# AD4111_2.net
KiCad netlist of a schematic drawn in Altium Designer
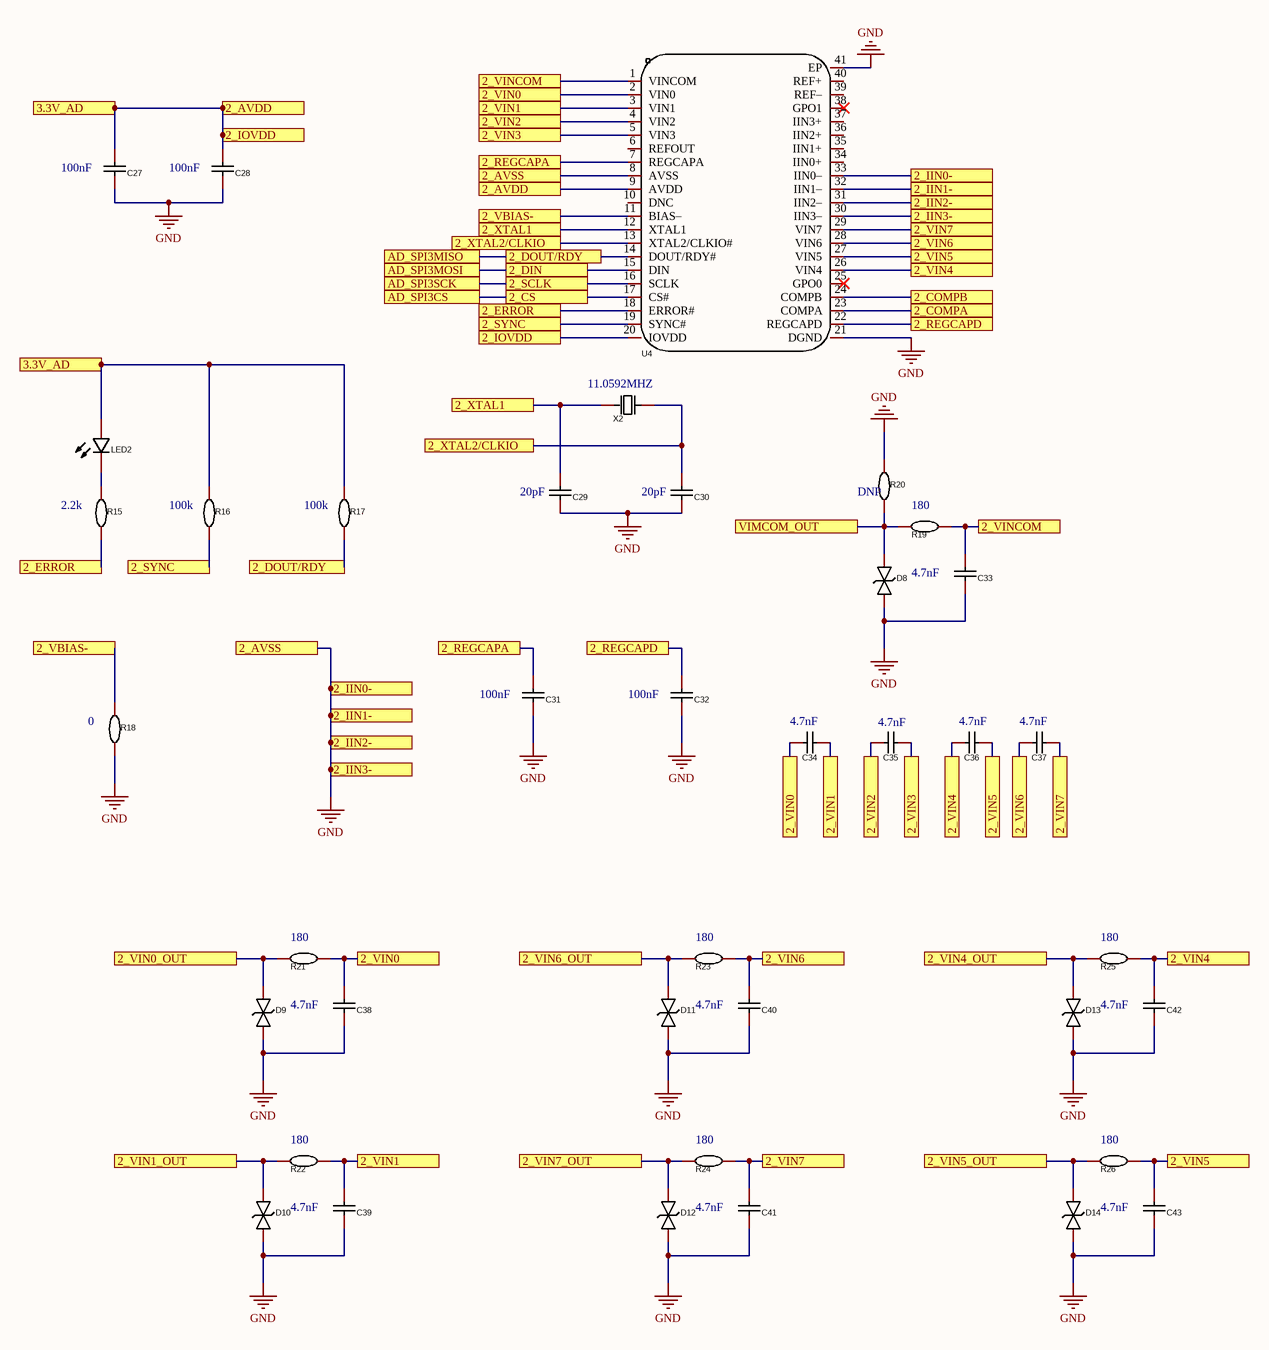
[diagram p0: AD4111_2.SchDoc]

(export (version "E")
  (design (tool "Eeschema 10.0.6"))
  (components
    (comp (ref "C27")
      (value "100nF")
      (footprint "C0603")
      (description "0603电容")
      (fields (field (name "MANUFACTURER") "FH(风华)") (field (name "MANUFACTURER PART") "0603B104K500NT"))
      (libsource (lib "LC_Components") (part "0603B104K500NT"))
    )
    (comp (ref "C28")
      (value "100nF")
      (footprint "C0603")
      (description "0603电容")
      (fields (field (name "MANUFACTURER") "FH(风华)") (field (name "MANUFACTURER PART") "0603B104K500NT"))
      (libsource (lib "LC_Components") (part "0603B104K500NT"))
    )
    (comp (ref "C29")
      (value "20pF")
      (footprint "C0603")
      (description "0603电容")
      (fields (field (name "MANUFACTURER") "FH(风华)") (field (name "MANUFACTURER PART") "0603B104K500NT"))
      (libsource (lib "LC_Components") (part "0603B104K500NT"))
    )
    (comp (ref "C30")
      (value "20pF")
      (footprint "C0603")
      (description "0603电容")
      (fields (field (name "MANUFACTURER") "FH(风华)") (field (name "MANUFACTURER PART") "0603B104K500NT"))
      (libsource (lib "LC_Components") (part "0603B104K500NT"))
    )
    (comp (ref "C31")
      (value "100nF")
      (footprint "C0603")
      (description "0603电容")
      (fields (field (name "MANUFACTURER") "FH(风华)") (field (name "MANUFACTURER PART") "0603B104K500NT"))
      (libsource (lib "LC_Components") (part "0603B104K500NT"))
    )
    (comp (ref "C32")
      (value "100nF")
      (footprint "C0603")
      (description "0603电容")
      (fields (field (name "MANUFACTURER") "FH(风华)") (field (name "MANUFACTURER PART") "0603B104K500NT"))
      (libsource (lib "LC_Components") (part "0603B104K500NT"))
    )
    (comp (ref "C33")
      (value "4.7nF")
      (footprint "C0603")
      (description "0603电容")
      (fields (field (name "MANUFACTURER") "FH(风华)") (field (name "MANUFACTURER PART") "0603B104K500NT"))
      (libsource (lib "LC_Components") (part "0603B104K500NT"))
    )
    (comp (ref "C34")
      (value "4.7nF")
      (footprint "C0603")
      (description "0603电容")
      (fields (field (name "MANUFACTURER") "FH(风华)") (field (name "MANUFACTURER PART") "0603B104K500NT"))
      (libsource (lib "LC_Components") (part "0603B104K500NT"))
    )
    (comp (ref "C35")
      (value "4.7nF")
      (footprint "C0603")
      (description "0603电容")
      (fields (field (name "MANUFACTURER") "FH(风华)") (field (name "MANUFACTURER PART") "0603B104K500NT"))
      (libsource (lib "LC_Components") (part "0603B104K500NT"))
    )
    (comp (ref "C36")
      (value "4.7nF")
      (footprint "C0603")
      (description "0603电容")
      (fields (field (name "MANUFACTURER") "FH(风华)") (field (name "MANUFACTURER PART") "0603B104K500NT"))
      (libsource (lib "LC_Components") (part "0603B104K500NT"))
    )
    (comp (ref "C37")
      (value "4.7nF")
      (footprint "C0603")
      (description "0603电容")
      (fields (field (name "MANUFACTURER") "FH(风华)") (field (name "MANUFACTURER PART") "0603B104K500NT"))
      (libsource (lib "LC_Components") (part "0603B104K500NT"))
    )
    (comp (ref "C38")
      (value "4.7nF")
      (footprint "C0603")
      (description "0603电容")
      (fields (field (name "MANUFACTURER") "FH(风华)") (field (name "MANUFACTURER PART") "0603B104K500NT"))
      (libsource (lib "LC_Components") (part "0603B104K500NT"))
    )
    (comp (ref "C39")
      (value "4.7nF")
      (footprint "C0603")
      (description "0603电容")
      (fields (field (name "MANUFACTURER") "FH(风华)") (field (name "MANUFACTURER PART") "0603B104K500NT"))
      (libsource (lib "LC_Components") (part "0603B104K500NT"))
    )
    (comp (ref "C40")
      (value "4.7nF")
      (footprint "C0603")
      (description "0603电容")
      (fields (field (name "MANUFACTURER") "FH(风华)") (field (name "MANUFACTURER PART") "0603B104K500NT"))
      (libsource (lib "LC_Components") (part "0603B104K500NT"))
    )
    (comp (ref "C41")
      (value "4.7nF")
      (footprint "C0603")
      (description "0603电容")
      (fields (field (name "MANUFACTURER") "FH(风华)") (field (name "MANUFACTURER PART") "0603B104K500NT"))
      (libsource (lib "LC_Components") (part "0603B104K500NT"))
    )
    (comp (ref "C42")
      (value "4.7nF")
      (footprint "C0603")
      (description "0603电容")
      (fields (field (name "MANUFACTURER") "FH(风华)") (field (name "MANUFACTURER PART") "0603B104K500NT"))
      (libsource (lib "LC_Components") (part "0603B104K500NT"))
    )
    (comp (ref "C43")
      (value "4.7nF")
      (footprint "C0603")
      (description "0603电容")
      (fields (field (name "MANUFACTURER") "FH(风华)") (field (name "MANUFACTURER PART") "0603B104K500NT"))
      (libsource (lib "LC_Components") (part "0603B104K500NT"))
    )
    (comp (ref "D8")
      (value "SMAJ33CA_C908829")
      (footprint "SMA_L4.4-W2.8-LS5.1-BI")
      (description "SMAJ33CA")
      (fields (field (name "MANUFACTURER") "GOODWORK(固得沃克)"))
      (libsource (lib "LC_Components") (part "SMAJ33CA_C908829"))
    )
    (comp (ref "D9")
      (value "SMAJ33CA_C908829")
      (footprint "SMA_L4.4-W2.8-LS5.1-BI")
      (description "SMAJ33CA")
      (fields (field (name "MANUFACTURER") "GOODWORK(固得沃克)"))
      (libsource (lib "LC_Components") (part "SMAJ33CA_C908829"))
    )
    (comp (ref "D10")
      (value "SMAJ33CA_C908829")
      (footprint "SMA_L4.4-W2.8-LS5.1-BI")
      (description "SMAJ33CA")
      (fields (field (name "MANUFACTURER") "GOODWORK(固得沃克)"))
      (libsource (lib "LC_Components") (part "SMAJ33CA_C908829"))
    )
    (comp (ref "D11")
      (value "SMAJ33CA_C908829")
      (footprint "SMA_L4.4-W2.8-LS5.1-BI")
      (description "SMAJ33CA")
      (fields (field (name "MANUFACTURER") "GOODWORK(固得沃克)"))
      (libsource (lib "LC_Components") (part "SMAJ33CA_C908829"))
    )
    (comp (ref "D12")
      (value "SMAJ33CA_C908829")
      (footprint "SMA_L4.4-W2.8-LS5.1-BI")
      (description "SMAJ33CA")
      (fields (field (name "MANUFACTURER") "GOODWORK(固得沃克)"))
      (libsource (lib "LC_Components") (part "SMAJ33CA_C908829"))
    )
    (comp (ref "D13")
      (value "SMAJ33CA_C908829")
      (footprint "SMA_L4.4-W2.8-LS5.1-BI")
      (description "SMAJ33CA")
      (fields (field (name "MANUFACTURER") "GOODWORK(固得沃克)"))
      (libsource (lib "LC_Components") (part "SMAJ33CA_C908829"))
    )
    (comp (ref "D14")
      (value "SMAJ33CA_C908829")
      (footprint "SMA_L4.4-W2.8-LS5.1-BI")
      (description "SMAJ33CA")
      (fields (field (name "MANUFACTURER") "GOODWORK(固得沃克)"))
      (libsource (lib "LC_Components") (part "SMAJ33CA_C908829"))
    )
    (comp (ref "LED2")
      (value "NCD0603R1_C84263")
      (footprint "LED0603-RD_RED")
      (description "LED")
      (fields (field (name "MANUFACTURER") "国星光电") (field (name "MANUFACTURER PART") "NCD0603R1"))
      (libsource (lib "LC_Components") (part "NCD0603R1_C84263"))
    )
    (comp (ref "R15")
      (value "2.2k")
      (footprint "R0603")
      (description "0603电阻")
      (fields
        (field (name "MANUFACTURER") "UNI-ROYAL(厚声)")
        (field (name "MANUFACTURER PART") "0603WAF1002T5E")
      )
      (libsource (lib "LC_Components") (part "0603WAF1002T5E"))
    )
    (comp (ref "R16")
      (value "100k")
      (footprint "R0603")
      (description "0603电阻")
      (fields
        (field (name "MANUFACTURER") "UNI-ROYAL(厚声)")
        (field (name "MANUFACTURER PART") "0603WAF1002T5E")
      )
      (libsource (lib "LC_Components") (part "0603WAF1002T5E"))
    )
    (comp (ref "R17")
      (value "100k")
      (footprint "R0603")
      (description "0603电阻")
      (fields
        (field (name "MANUFACTURER") "UNI-ROYAL(厚声)")
        (field (name "MANUFACTURER PART") "0603WAF1002T5E")
      )
      (libsource (lib "LC_Components") (part "0603WAF1002T5E"))
    )
    (comp (ref "R18")
      (value "0")
      (footprint "R0603")
      (description "0603电阻")
      (fields
        (field (name "MANUFACTURER") "UNI-ROYAL(厚声)")
        (field (name "MANUFACTURER PART") "0603WAF1002T5E")
      )
      (libsource (lib "LC_Components") (part "0603WAF1002T5E"))
    )
    (comp (ref "R19")
      (value "180")
      (footprint "R0603")
      (description "0603电阻")
      (fields
        (field (name "MANUFACTURER") "UNI-ROYAL(厚声)")
        (field (name "MANUFACTURER PART") "0603WAF1002T5E")
      )
      (libsource (lib "LC_Components") (part "0603WAF1002T5E"))
    )
    (comp (ref "R20")
      (value "DNP")
      (footprint "R0603")
      (description "0603电阻")
      (fields
        (field (name "MANUFACTURER") "UNI-ROYAL(厚声)")
        (field (name "MANUFACTURER PART") "0603WAF1002T5E")
      )
      (libsource (lib "LC_Components") (part "0603WAF1002T5E"))
    )
    (comp (ref "R21")
      (value "180")
      (footprint "R0603")
      (description "0603电阻")
      (fields
        (field (name "MANUFACTURER") "UNI-ROYAL(厚声)")
        (field (name "MANUFACTURER PART") "0603WAF1002T5E")
      )
      (libsource (lib "LC_Components") (part "0603WAF1002T5E"))
    )
    (comp (ref "R22")
      (value "180")
      (footprint "R0603")
      (description "0603电阻")
      (fields
        (field (name "MANUFACTURER") "UNI-ROYAL(厚声)")
        (field (name "MANUFACTURER PART") "0603WAF1002T5E")
      )
      (libsource (lib "LC_Components") (part "0603WAF1002T5E"))
    )
    (comp (ref "R23")
      (value "180")
      (footprint "R0603")
      (description "0603电阻")
      (fields
        (field (name "MANUFACTURER") "UNI-ROYAL(厚声)")
        (field (name "MANUFACTURER PART") "0603WAF1002T5E")
      )
      (libsource (lib "LC_Components") (part "0603WAF1002T5E"))
    )
    (comp (ref "R24")
      (value "180")
      (footprint "R0603")
      (description "0603电阻")
      (fields
        (field (name "MANUFACTURER") "UNI-ROYAL(厚声)")
        (field (name "MANUFACTURER PART") "0603WAF1002T5E")
      )
      (libsource (lib "LC_Components") (part "0603WAF1002T5E"))
    )
    (comp (ref "R25")
      (value "180")
      (footprint "R0603")
      (description "0603电阻")
      (fields
        (field (name "MANUFACTURER") "UNI-ROYAL(厚声)")
        (field (name "MANUFACTURER PART") "0603WAF1002T5E")
      )
      (libsource (lib "LC_Components") (part "0603WAF1002T5E"))
    )
    (comp (ref "R26")
      (value "180")
      (footprint "R0603")
      (description "0603电阻")
      (fields
        (field (name "MANUFACTURER") "UNI-ROYAL(厚声)")
        (field (name "MANUFACTURER PART") "0603WAF1002T5E")
      )
      (libsource (lib "LC_Components") (part "0603WAF1002T5E"))
    )
    (comp (ref "U4")
      (value "AD4111BCPZ")
      (footprint "LFCSP-40_L6.0-W6.0-P0.50-TL-EP4.6")
      (fields (field (name "MANUFACTURER") "ADI(亚德诺)"))
      (libsource (lib "LC_Components") (part "AD4111BCPZ"))
    )
    (comp (ref "X2")
      (value "11.0592MHZ")
      (footprint "OSC-SMD_L5.0-W3.2")
      (description "11.0592MHZ晶振")
      (fields
        (field (name "MANUFACTURER") "YXC(扬兴晶振)")
        (field (name "MANUFACTURER PART") "X5032110592MSB2GI")
      )
      (libsource (lib "LC_Components") (part "X5032110592MSB2GI"))
    )
  )
  (nets
    (net (code "1") (name "/2_AVDD") (class "Default")
      (node (ref "C27") (pin "2") (pinfunction "2_2") (pintype "passive"))
      (node (ref "C28") (pin "2") (pinfunction "2_2") (pintype "passive"))
      (node (ref "LED2") (pin "2") (pinfunction "A_2") (pintype "passive"))
      (node (ref "R16") (pin "2") (pinfunction "2_2") (pintype "passive"))
      (node (ref "R17") (pin "2") (pinfunction "2_2") (pintype "passive"))
      (node (ref "U4") (pin "20") (pinfunction "IOVDD_20") (pintype "passive"))
      (node (ref "U4") (pin "9") (pinfunction "AVDD_9") (pintype "passive"))
    )
    (net (code "2") (name "/2_COMPA") (class "Default")
      (node (ref "U4") (pin "23") (pinfunction "COMPA_23") (pintype "passive"))
    )
    (net (code "3") (name "/2_COMPB") (class "Default")
      (node (ref "U4") (pin "24") (pinfunction "COMPB_24") (pintype "passive"))
    )
    (net (code "4") (name "/2_CS") (class "Default")
      (node (ref "U4") (pin "17") (pinfunction "CS#_17") (pintype "passive"))
    )
    (net (code "5") (name "/2_DIN") (class "Default")
      (node (ref "U4") (pin "15") (pinfunction "DIN_15") (pintype "passive"))
    )
    (net (code "6") (name "/2_DOUT{slash}RDY") (class "Default")
      (node (ref "R17") (pin "1") (pinfunction "1_1") (pintype "passive"))
      (node (ref "U4") (pin "14") (pinfunction "DOUT/RDY#_14") (pintype "passive"))
    )
    (net (code "7") (name "/2_ERROR") (class "Default")
      (node (ref "R15") (pin "1") (pinfunction "1_1") (pintype "passive"))
      (node (ref "U4") (pin "18") (pinfunction "ERROR#_18") (pintype "passive"))
    )
    (net (code "8") (name "/2_REGCAPA") (class "Default")
      (node (ref "C31") (pin "2") (pinfunction "2_2") (pintype "passive"))
      (node (ref "U4") (pin "7") (pinfunction "REGCAPA_7") (pintype "passive"))
    )
    (net (code "9") (name "/2_REGCAPD") (class "Default")
      (node (ref "C32") (pin "2") (pinfunction "2_2") (pintype "passive"))
      (node (ref "U4") (pin "22") (pinfunction "REGCAPD_22") (pintype "passive"))
    )
    (net (code "10") (name "/2_SCLK") (class "Default")
      (node (ref "U4") (pin "16") (pinfunction "SCLK_16") (pintype "passive"))
    )
    (net (code "11") (name "/2_SYNC") (class "Default")
      (node (ref "R16") (pin "1") (pinfunction "1_1") (pintype "passive"))
      (node (ref "U4") (pin "19") (pinfunction "SYNC#_19") (pintype "passive"))
    )
    (net (code "12") (name "/2_VBIAS-") (class "Default")
      (node (ref "R18") (pin "2") (pinfunction "2_2") (pintype "passive"))
      (node (ref "U4") (pin "11") (pinfunction "BIAS–_11") (pintype "passive"))
    )
    (net (code "13") (name "/2_VIN0") (class "Default")
      (node (ref "C34") (pin "1") (pinfunction "1_1") (pintype "passive"))
      (node (ref "C38") (pin "2") (pinfunction "2_2") (pintype "passive"))
      (node (ref "R21") (pin "2") (pinfunction "2_2") (pintype "passive"))
      (node (ref "U4") (pin "2") (pinfunction "VIN0_2") (pintype "passive"))
    )
    (net (code "14") (name "/2_VIN0_OUT") (class "Default")
      (node (ref "D9") (pin "1") (pinfunction "1_1") (pintype "passive"))
      (node (ref "R21") (pin "1") (pinfunction "1_1") (pintype "passive"))
    )
    (net (code "15") (name "/2_VIN1") (class "Default")
      (node (ref "C34") (pin "2") (pinfunction "2_2") (pintype "passive"))
      (node (ref "C39") (pin "2") (pinfunction "2_2") (pintype "passive"))
      (node (ref "R22") (pin "2") (pinfunction "2_2") (pintype "passive"))
      (node (ref "U4") (pin "3") (pinfunction "VIN1_3") (pintype "passive"))
    )
    (net (code "16") (name "/2_VIN1_OUT") (class "Default")
      (node (ref "D10") (pin "1") (pinfunction "1_1") (pintype "passive"))
      (node (ref "R22") (pin "1") (pinfunction "1_1") (pintype "passive"))
    )
    (net (code "17") (name "/2_VIN2") (class "Default")
      (node (ref "C35") (pin "1") (pinfunction "1_1") (pintype "passive"))
      (node (ref "U4") (pin "4") (pinfunction "VIN2_4") (pintype "passive"))
    )
    (net (code "18") (name "/2_VIN3") (class "Default")
      (node (ref "C35") (pin "2") (pinfunction "2_2") (pintype "passive"))
      (node (ref "U4") (pin "5") (pinfunction "VIN3_5") (pintype "passive"))
    )
    (net (code "19") (name "/2_VIN4") (class "Default")
      (node (ref "C36") (pin "1") (pinfunction "1_1") (pintype "passive"))
      (node (ref "C42") (pin "2") (pinfunction "2_2") (pintype "passive"))
      (node (ref "R25") (pin "2") (pinfunction "2_2") (pintype "passive"))
      (node (ref "U4") (pin "26") (pinfunction "VIN4_26") (pintype "passive"))
    )
    (net (code "20") (name "/2_VIN4_OUT") (class "Default")
      (node (ref "D13") (pin "1") (pinfunction "1_1") (pintype "passive"))
      (node (ref "R25") (pin "1") (pinfunction "1_1") (pintype "passive"))
    )
    (net (code "21") (name "/2_VIN5") (class "Default")
      (node (ref "C36") (pin "2") (pinfunction "2_2") (pintype "passive"))
      (node (ref "C43") (pin "2") (pinfunction "2_2") (pintype "passive"))
      (node (ref "R26") (pin "2") (pinfunction "2_2") (pintype "passive"))
      (node (ref "U4") (pin "27") (pinfunction "VIN5_27") (pintype "passive"))
    )
    (net (code "22") (name "/2_VIN5_OUT") (class "Default")
      (node (ref "D14") (pin "1") (pinfunction "1_1") (pintype "passive"))
      (node (ref "R26") (pin "1") (pinfunction "1_1") (pintype "passive"))
    )
    (net (code "23") (name "/2_VIN6") (class "Default")
      (node (ref "C37") (pin "1") (pinfunction "1_1") (pintype "passive"))
      (node (ref "C40") (pin "2") (pinfunction "2_2") (pintype "passive"))
      (node (ref "R23") (pin "2") (pinfunction "2_2") (pintype "passive"))
      (node (ref "U4") (pin "28") (pinfunction "VIN6_28") (pintype "passive"))
    )
    (net (code "24") (name "/2_VIN6_OUT") (class "Default")
      (node (ref "D11") (pin "1") (pinfunction "1_1") (pintype "passive"))
      (node (ref "R23") (pin "1") (pinfunction "1_1") (pintype "passive"))
    )
    (net (code "25") (name "/2_VIN7") (class "Default")
      (node (ref "C37") (pin "2") (pinfunction "2_2") (pintype "passive"))
      (node (ref "C41") (pin "2") (pinfunction "2_2") (pintype "passive"))
      (node (ref "R24") (pin "2") (pinfunction "2_2") (pintype "passive"))
      (node (ref "U4") (pin "29") (pinfunction "VIN7_29") (pintype "passive"))
    )
    (net (code "26") (name "/2_VIN7_OUT") (class "Default")
      (node (ref "D12") (pin "1") (pinfunction "1_1") (pintype "passive"))
      (node (ref "R24") (pin "1") (pinfunction "1_1") (pintype "passive"))
    )
    (net (code "27") (name "/2_VINCOM") (class "Default")
      (node (ref "C33") (pin "2") (pinfunction "2_2") (pintype "passive"))
      (node (ref "R19") (pin "2") (pinfunction "2_2") (pintype "passive"))
      (node (ref "U4") (pin "1") (pinfunction "VINCOM_1") (pintype "passive"))
    )
    (net (code "28") (name "/2_XTAL1") (class "Default")
      (node (ref "C29") (pin "2") (pinfunction "2_2") (pintype "passive"))
      (node (ref "U4") (pin "12") (pinfunction "XTAL1_12") (pintype "passive"))
      (node (ref "X2") (pin "1") (pinfunction "OSC1_1") (pintype "passive"))
    )
    (net (code "29") (name "/2_XTAL2{slash}CLKIO") (class "Default")
      (node (ref "C30") (pin "2") (pinfunction "2_2") (pintype "passive"))
      (node (ref "U4") (pin "13") (pinfunction "XTAL2/CLKIO#_13") (pintype "passive"))
      (node (ref "X2") (pin "2") (pinfunction "OSC2_2") (pintype "passive"))
    )
    (net (code "30") (name "/VIMCOM_OUT") (class "Default")
      (node (ref "D8") (pin "1") (pinfunction "1_1") (pintype "passive"))
      (node (ref "R19") (pin "1") (pinfunction "1_1") (pintype "passive"))
      (node (ref "R20") (pin "1") (pinfunction "1_1") (pintype "passive"))
    )
    (net (code "31") (name "GND") (class "Default")
      (node (ref "C27") (pin "1") (pinfunction "1_1") (pintype "passive"))
      (node (ref "C28") (pin "1") (pinfunction "1_1") (pintype "passive"))
      (node (ref "C29") (pin "1") (pinfunction "1_1") (pintype "passive"))
      (node (ref "C30") (pin "1") (pinfunction "1_1") (pintype "passive"))
      (node (ref "C31") (pin "1") (pinfunction "1_1") (pintype "passive"))
      (node (ref "C32") (pin "1") (pinfunction "1_1") (pintype "passive"))
      (node (ref "C33") (pin "1") (pinfunction "1_1") (pintype "passive"))
      (node (ref "C38") (pin "1") (pinfunction "1_1") (pintype "passive"))
      (node (ref "C39") (pin "1") (pinfunction "1_1") (pintype "passive"))
      (node (ref "C40") (pin "1") (pinfunction "1_1") (pintype "passive"))
      (node (ref "C41") (pin "1") (pinfunction "1_1") (pintype "passive"))
      (node (ref "C42") (pin "1") (pinfunction "1_1") (pintype "passive"))
      (node (ref "C43") (pin "1") (pinfunction "1_1") (pintype "passive"))
      (node (ref "D10") (pin "2") (pinfunction "2_2") (pintype "passive"))
      (node (ref "D11") (pin "2") (pinfunction "2_2") (pintype "passive"))
      (node (ref "D12") (pin "2") (pinfunction "2_2") (pintype "passive"))
      (node (ref "D13") (pin "2") (pinfunction "2_2") (pintype "passive"))
      (node (ref "D14") (pin "2") (pinfunction "2_2") (pintype "passive"))
      (node (ref "D8") (pin "2") (pinfunction "2_2") (pintype "passive"))
      (node (ref "D9") (pin "2") (pinfunction "2_2") (pintype "passive"))
      (node (ref "R18") (pin "1") (pinfunction "1_1") (pintype "passive"))
      (node (ref "R20") (pin "2") (pinfunction "2_2") (pintype "passive"))
      (node (ref "U4") (pin "21") (pinfunction "DGND_21") (pintype "passive"))
      (node (ref "U4") (pin "30") (pinfunction "IIN3–_30") (pintype "passive"))
      (node (ref "U4") (pin "31") (pinfunction "IIN2–_31") (pintype "passive"))
      (node (ref "U4") (pin "32") (pinfunction "IIN1–_32") (pintype "passive"))
      (node (ref "U4") (pin "33") (pinfunction "IIN0–_33") (pintype "passive"))
      (node (ref "U4") (pin "41") (pinfunction "EP_41") (pintype "passive"))
      (node (ref "U4") (pin "8") (pinfunction "AVSS_8") (pintype "passive"))
    )
    (net (code "32") (name "Net-(LED2-K)") (class "Default")
      (node (ref "LED2") (pin "1") (pinfunction "K_1") (pintype "passive"))
      (node (ref "R15") (pin "2") (pinfunction "2_2") (pintype "passive"))
    )
    (net (code "33") (name "unconnected-(U4-DNC-Pad10)") (class "Default")
      (node (ref "U4") (pin "10") (pinfunction "DNC_10") (pintype "passive"))
    )
    (net (code "34") (name "unconnected-(U4-GPO0-Pad25)") (class "Default")
      (node (ref "U4") (pin "25") (pinfunction "GPO0_25") (pintype "passive+no_connect"))
    )
    (net (code "35") (name "unconnected-(U4-GPO1-Pad38)") (class "Default")
      (node (ref "U4") (pin "38") (pinfunction "GPO1_38") (pintype "passive+no_connect"))
    )
    (net (code "36") (name "unconnected-(U4-IIN0+-Pad34)") (class "Default")
      (node (ref "U4") (pin "34") (pinfunction "IIN0+_34") (pintype "passive"))
    )
    (net (code "37") (name "unconnected-(U4-IIN1+-Pad35)") (class "Default")
      (node (ref "U4") (pin "35") (pinfunction "IIN1+_35") (pintype "passive"))
    )
    (net (code "38") (name "unconnected-(U4-IIN2+-Pad36)") (class "Default")
      (node (ref "U4") (pin "36") (pinfunction "IIN2+_36") (pintype "passive"))
    )
    (net (code "39") (name "unconnected-(U4-IIN3+-Pad37)") (class "Default")
      (node (ref "U4") (pin "37") (pinfunction "IIN3+_37") (pintype "passive"))
    )
    (net (code "40") (name "unconnected-(U4-REF+-Pad40)") (class "Default")
      (node (ref "U4") (pin "40") (pinfunction "REF+_40") (pintype "passive"))
    )
    (net (code "41") (name "unconnected-(U4-REFOUT-Pad6)") (class "Default")
      (node (ref "U4") (pin "6") (pinfunction "REFOUT_6") (pintype "passive"))
    )
    (net (code "42") (name "unconnected-(U4-REF–-Pad39)") (class "Default")
      (node (ref "U4") (pin "39") (pinfunction "REF–_39") (pintype "passive"))
    )
  )
)
